# VREG_AOZ1284PI_4V2_4A.net
KiCad netlist of a schematic drawn in Altium Designer
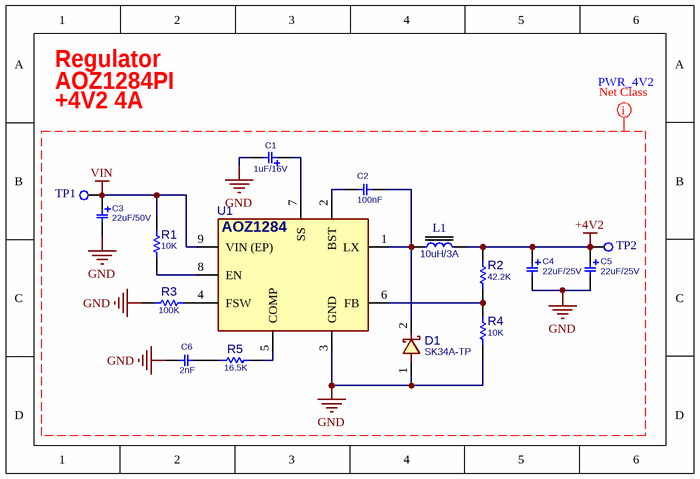
[diagram p0: VREG AOZ1284PI +4V2 4A.SchDoc]

(export (version "E")
  (design (tool "Eeschema 10.0.6"))
  (components
    (comp (ref "C1")
      (value "1uF/16V")
      (footprint "C_TN_A")
      (description "CAP, SMD, TAN")
      (libsource (lib "Passive") (part "CAP_SMD_TAN"))
    )
    (comp (ref "C2")
      (value "100nF")
      (footprint "C0603S")
      (description "CAP, SMD, MLCC")
      (fields (field (name "MANF_P#") "MANF_PART#") (field (name "MANF") "Murata"))
      (libsource (lib "Passive") (part "CAP_SMD_MLCC"))
    )
    (comp (ref "C3")
      (value "22uF/50V")
      (footprint "C_TN_A")
      (description "CAP, SMD, TAN")
      (libsource (lib "Passive") (part "CAP_SMD_TAN"))
    )
    (comp (ref "C4")
      (value "22uF/25V")
      (footprint "C_TN_A")
      (description "CAP, SMD, TAN")
      (libsource (lib "Passive") (part "CAP_SMD_TAN"))
    )
    (comp (ref "C5")
      (value "22uF/25V")
      (footprint "C_TN_A")
      (description "CAP, SMD, TAN")
      (libsource (lib "Passive") (part "CAP_SMD_TAN"))
    )
    (comp (ref "C6")
      (value "2nF")
      (footprint "C0603S")
      (description "CAP, SMD, MLCC")
      (fields (field (name "MANF_P#") "MANF_PART#") (field (name "MANF") "Murata"))
      (libsource (lib "Passive") (part "CAP_SMD_MLCC"))
    )
    (comp (ref "D1")
      (value "SK34A-TP")
      (footprint "D_SMA")
      (description "DIODE, SCHOTTKY, 40V, 3A")
      (fields (field (name "MANF") "Vishay") (field (name "MANF_P#") "SS14-E3"))
      (libsource (lib "PW Components 97_492") (part "DIODE_SMD_SCHOTTKY_SK34A-TP"))
    )
    (comp (ref "L1")
      (value "10uH/3A")
      (footprint "L_8X8")
      (description "IND, PWR, SMD")
      (libsource (lib "Passive") (part "INDPWR_SMD"))
    )
    (comp (ref "R1")
      (value "10K")
      (footprint "R0603S")
      (description "RES, SMD")
      (fields (field (name "MANF_P#") "RK73H1ETTP4701F") (field (name "MANF") "KOA SPEER"))
      (libsource (lib "Passive") (part "RES_SMD"))
    )
    (comp (ref "R2")
      (value "42.2K")
      (footprint "R0603S")
      (description "RES, SMD")
      (fields (field (name "MANF_P#") "RK73H1ETTP4701F") (field (name "MANF") "KOA SPEER"))
      (libsource (lib "Passive") (part "RES_SMD"))
    )
    (comp (ref "R3")
      (value "100K")
      (footprint "R0603S")
      (description "RES, SMD")
      (fields (field (name "MANF_P#") "RK73H1ETTP4701F") (field (name "MANF") "KOA SPEER"))
      (libsource (lib "Passive") (part "RES_SMD"))
    )
    (comp (ref "R4")
      (value "10K")
      (footprint "R0603S")
      (description "RES, SMD")
      (fields (field (name "MANF_P#") "RK73H1ETTP4701F") (field (name "MANF") "KOA SPEER"))
      (libsource (lib "Passive") (part "RES_SMD"))
    )
    (comp (ref "R5")
      (value "16.5K")
      (footprint "R0603S")
      (description "RES, SMD")
      (fields (field (name "MANF_P#") "RK73H1ETTP4701F") (field (name "MANF") "KOA SPEER"))
      (libsource (lib "Passive") (part "RES_SMD"))
    )
    (comp (ref "TP1")
      (value "Test Point")
      (footprint "TPSMD_C1")
      (libsource (lib "PW Components") (part "Test Point"))
    )
    (comp (ref "TP2")
      (value "Test Point")
      (footprint "TPSMD_C1")
      (libsource (lib "PW Components") (part "Test Point"))
    )
    (comp (ref "U1")
      (value "AOZ1021AI")
      (footprint "SO_8T")
      (description "REG, Switching, Buck, 4A, ADJ, 500KHz, 3~36VIN, SO-8")
      (fields (field (name "MANF") "AOSMD"))
      (libsource (lib "PW Components 97_492") (part "VREG_AOZ1284PI_SO8"))
    )
  )
  (nets
    (net (code "1") (name "+4V2") (class "Default")
      (node (ref "C4") (pin "1") (pinfunction "1_1") (pintype "passive"))
      (node (ref "C5") (pin "1") (pinfunction "1_1") (pintype "passive"))
      (node (ref "L1") (pin "2") (pinfunction "2_2") (pintype "passive"))
      (node (ref "R2") (pin "1") (pinfunction "1_1") (pintype "passive"))
      (node (ref "TP2") (pin "1") (pinfunction "TP_1") (pintype "passive"))
    )
    (net (code "2") (name "GND") (class "Default")
      (node (ref "C1") (pin "2") (pinfunction "2_2") (pintype "passive"))
      (node (ref "C3") (pin "2") (pinfunction "2_2") (pintype "passive"))
      (node (ref "C4") (pin "2") (pinfunction "2_2") (pintype "passive"))
      (node (ref "C5") (pin "2") (pinfunction "2_2") (pintype "passive"))
      (node (ref "C6") (pin "2") (pinfunction "2_2") (pintype "passive"))
      (node (ref "D1") (pin "1") (pinfunction "1_1") (pintype "passive"))
      (node (ref "R3") (pin "1") (pinfunction "1_1") (pintype "passive"))
      (node (ref "R4") (pin "2") (pinfunction "2_2") (pintype "passive"))
      (node (ref "U1") (pin "3") (pinfunction "GND_3") (pintype "power_in"))
    )
    (net (code "3") (name "Net-(C6-Pad1)") (class "Default")
      (node (ref "C6") (pin "1") (pinfunction "1_1") (pintype "passive"))
      (node (ref "R5") (pin "1") (pinfunction "1_1") (pintype "passive"))
    )
    (net (code "4") (name "Net-(U1-BST)") (class "Default")
      (node (ref "C2") (pin "2") (pinfunction "2_2") (pintype "passive"))
      (node (ref "U1") (pin "2") (pinfunction "BST_2") (pintype "passive"))
    )
    (net (code "5") (name "Net-(U1-COMP)") (class "Default")
      (node (ref "R5") (pin "2") (pinfunction "2_2") (pintype "passive"))
      (node (ref "U1") (pin "5") (pinfunction "COMP_5") (pintype "power_in"))
    )
    (net (code "6") (name "Net-(U1-EN)") (class "Default")
      (node (ref "R1") (pin "2") (pinfunction "2_2") (pintype "passive"))
      (node (ref "U1") (pin "8") (pinfunction "EN_8") (pintype "passive"))
    )
    (net (code "7") (name "Net-(U1-FB)") (class "Default")
      (node (ref "R2") (pin "2") (pinfunction "2_2") (pintype "passive"))
      (node (ref "R4") (pin "1") (pinfunction "1_1") (pintype "passive"))
      (node (ref "U1") (pin "6") (pinfunction "FB_6") (pintype "passive"))
    )
    (net (code "8") (name "Net-(U1-FSW)") (class "Default")
      (node (ref "R3") (pin "2") (pinfunction "2_2") (pintype "passive"))
      (node (ref "U1") (pin "4") (pinfunction "FSW_4") (pintype "passive"))
    )
    (net (code "9") (name "Net-(U1-LX)") (class "Default")
      (node (ref "C2") (pin "1") (pinfunction "1_1") (pintype "passive"))
      (node (ref "D1") (pin "2") (pinfunction "2_2") (pintype "passive"))
      (node (ref "L1") (pin "1") (pinfunction "1_1") (pintype "passive"))
      (node (ref "U1") (pin "1") (pinfunction "LX_1") (pintype "passive"))
    )
    (net (code "10") (name "Net-(U1-SS)") (class "Default")
      (node (ref "C1") (pin "1") (pinfunction "1_1") (pintype "passive"))
      (node (ref "U1") (pin "7") (pinfunction "SS_7") (pintype "passive"))
    )
    (net (code "11") (name "VIN") (class "Default")
      (node (ref "C3") (pin "1") (pinfunction "1_1") (pintype "passive"))
      (node (ref "R1") (pin "1") (pinfunction "1_1") (pintype "passive"))
      (node (ref "TP1") (pin "1") (pinfunction "TP_1") (pintype "passive"))
      (node (ref "U1") (pin "9") (pinfunction "VIN_(EP)_9") (pintype "power_in"))
    )
  )
)
